# PCIe.net
KiCad netlist of a schematic drawn in Altium Designer
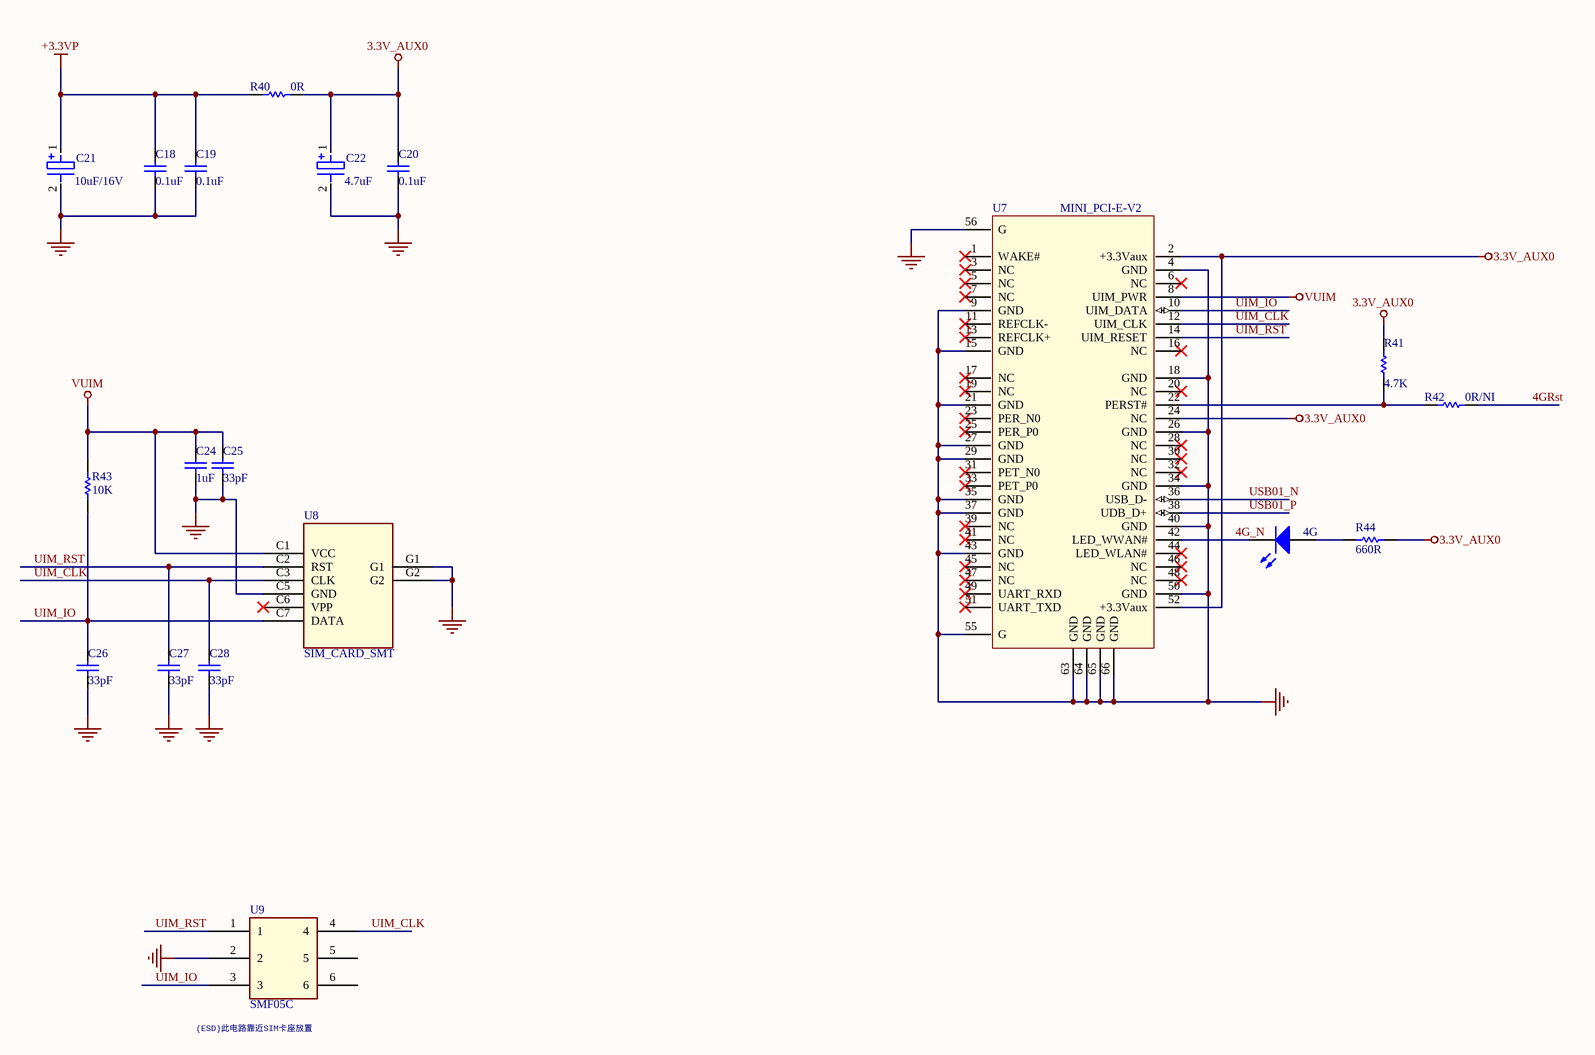
[diagram p0: PCIe.SchDoc]

(export (version "E")
  (design (tool "Eeschema 10.0.6"))
  (components
    (comp (ref "4G")
      (value "leds_0603")
      (footprint "0603LED")
      (libsource (lib "USB_SOUND") (part "leds_0603"))
    )
    (comp (ref "C18")
      (value "0.1uF")
      (footprint "C0603L")
      (description "Capacitor")
      (fields (field (name "Comment") "Cap Semi") (field (name "PUBLISHER") "Altium Limited"))
      (libsource (lib "Miscellaneous Devices") (part "Cap"))
    )
    (comp (ref "C19")
      (value "0.1uF")
      (footprint "C0603L")
      (description "Capacitor")
      (fields (field (name "Comment") "Cap Semi") (field (name "PUBLISHER") "Altium Limited"))
      (libsource (lib "Miscellaneous Devices") (part "Cap"))
    )
    (comp (ref "C20")
      (value "0.1uF")
      (footprint "C0603L")
      (description "Capacitor")
      (fields (field (name "Comment") "Cap Semi") (field (name "PUBLISHER") "Altium Limited"))
      (libsource (lib "Miscellaneous Devices") (part "Cap"))
    )
    (comp (ref "C21")
      (value "10uF/16V")
      (footprint "C0603L")
      (fields (field (name "Comment") "Cap Semi"))
      (libsource (lib "wooya_lib_footprint") (part "CAP3"))
    )
    (comp (ref "C22")
      (value "4.7uF")
      (footprint "C0603L")
      (fields (field (name "Comment") "Cap Semi"))
      (libsource (lib "wooya_lib_footprint") (part "CAP3"))
    )
    (comp (ref "C24")
      (value "1uF")
      (footprint "C0603L")
      (description "Capacitor (Semiconductor SIM Model)")
      (fields (field (name "Comment") "Cap Semi") (field (name "PUBLISHER") "Altium Limited"))
      (libsource (lib "Miscellaneous Devices") (part "Cap Semi"))
    )
    (comp (ref "C25")
      (value "33pF")
      (footprint "C0603L")
      (description "Capacitor (Semiconductor SIM Model)")
      (fields (field (name "Comment") "Cap Semi") (field (name "PUBLISHER") "Altium Limited"))
      (libsource (lib "Miscellaneous Devices") (part "Cap Semi"))
    )
    (comp (ref "C26")
      (value "33pF")
      (footprint "C0603L")
      (description "Capacitor (Semiconductor SIM Model)")
      (fields (field (name "Comment") "Cap Semi") (field (name "PUBLISHER") "Altium Limited"))
      (libsource (lib "Miscellaneous Devices") (part "Cap Semi"))
    )
    (comp (ref "C27")
      (value "33pF")
      (footprint "C0603L")
      (description "Capacitor (Semiconductor SIM Model)")
      (fields (field (name "Comment") "Cap Semi") (field (name "PUBLISHER") "Altium Limited"))
      (libsource (lib "Miscellaneous Devices") (part "Cap Semi"))
    )
    (comp (ref "C28")
      (value "33pF")
      (footprint "C0603L")
      (description "Capacitor (Semiconductor SIM Model)")
      (fields (field (name "Comment") "Cap Semi") (field (name "PUBLISHER") "Altium Limited"))
      (libsource (lib "Miscellaneous Devices") (part "Cap Semi"))
    )
    (comp (ref "R40")
      (value "0R")
      (footprint "R0603L")
      (description "Semiconductor Resistor")
      (fields (field (name "Comment") "Res Semi") (field (name "PUBLISHER") "Altium Limited"))
      (libsource (lib "Miscellaneous Devices") (part "Res Semi"))
    )
    (comp (ref "R41")
      (value "4.7K")
      (footprint "R0603L")
      (description "Semiconductor Resistor")
      (fields (field (name "Comment") "Res Semi") (field (name "PUBLISHER") "Altium Limited"))
      (libsource (lib "Miscellaneous Devices") (part "Res Semi"))
    )
    (comp (ref "R42")
      (value "0R/NI")
      (footprint "R0603L")
      (description "Semiconductor Resistor")
      (fields (field (name "Comment") "Res Semi") (field (name "PUBLISHER") "Altium Limited"))
      (libsource (lib "Miscellaneous Devices") (part "Res Semi"))
    )
    (comp (ref "R43")
      (value "10K")
      (footprint "R0603L")
      (description "Semiconductor Resistor")
      (fields (field (name "Comment") "Res Semi") (field (name "PUBLISHER") "Altium Limited"))
      (libsource (lib "Miscellaneous Devices") (part "Res Semi"))
    )
    (comp (ref "R44")
      (value "660R")
      (footprint "R0603L")
      (description "Semiconductor Resistor")
      (fields (field (name "Comment") "Res Semi") (field (name "PUBLISHER") "Altium Limited"))
      (libsource (lib "Miscellaneous Devices") (part "Res Semi"))
    )
    (comp (ref "U7")
      (value "MINI_PCI-E-V2")
      (footprint "MINI_PCI-E_V2")
      (libsource (lib "WOOYA_LIB_FOOTPRINT") (part "MINI_PCI-E-V2"))
    )
    (comp (ref "U8")
      (value "SIM_CARD_SMT")
      (footprint "SIM_CARD_SMT")
      (libsource (lib "wooya_lib_footprint") (part "SIM_CARD_SMT"))
    )
    (comp (ref "U9")
      (value "SMF05C")
      (footprint "SMF05C")
      (libsource (lib "wooya_lib_footprint") (part "SMF05C"))
    )
  )
  (nets
    (net (code "1") (name "+3.3VP") (class "Default")
      (node (ref "C18") (pin "2") (pinfunction "2_2") (pintype "passive"))
      (node (ref "C19") (pin "2") (pinfunction "2_2") (pintype "passive"))
      (node (ref "C21") (pin "1") (pinfunction "1_1") (pintype "passive"))
      (node (ref "R40") (pin "2") (pinfunction "2_2") (pintype "passive"))
    )
    (net (code "2") (name "/4GRst") (class "Default")
      (node (ref "R42") (pin "2") (pinfunction "2_2") (pintype "passive"))
    )
    (net (code "3") (name "/4G_N") (class "Default")
      (node (ref "4G") (pin "2") (pinfunction "K_2") (pintype "passive"))
      (node (ref "U7") (pin "42") (pinfunction "LED_WWAN#_42") (pintype "open_collector"))
    )
    (net (code "4") (name "/UIM_CLK") (class "Default")
      (node (ref "C28") (pin "1") (pinfunction "1_1") (pintype "passive"))
      (node (ref "U7") (pin "12") (pinfunction "UIM_CLK_12") (pintype "passive"))
      (node (ref "U8") (pin "C3") (pinfunction "CLK_C3") (pintype "passive"))
      (node (ref "U9") (pin "4") (pinfunction "4_4") (pintype "passive"))
    )
    (net (code "5") (name "/UIM_IO") (class "Default")
      (node (ref "C26") (pin "1") (pinfunction "1_1") (pintype "passive"))
      (node (ref "R43") (pin "1") (pinfunction "1_1") (pintype "passive"))
      (node (ref "U7") (pin "10") (pinfunction "UIM_DATA_10") (pintype "bidirectional"))
      (node (ref "U8") (pin "C7") (pinfunction "DATA_C7") (pintype "passive"))
      (node (ref "U9") (pin "3") (pinfunction "3_3") (pintype "passive"))
    )
    (net (code "6") (name "/UIM_RST") (class "Default")
      (node (ref "C27") (pin "1") (pinfunction "1_1") (pintype "passive"))
      (node (ref "U7") (pin "14") (pinfunction "UIM_RESET_14") (pintype "passive"))
      (node (ref "U8") (pin "C2") (pinfunction "RST_C2") (pintype "passive"))
      (node (ref "U9") (pin "1") (pinfunction "1_1") (pintype "passive"))
    )
    (net (code "7") (name "/USB01_N") (class "Default")
      (node (ref "U7") (pin "36") (pinfunction "USB_D-_36") (pintype "bidirectional"))
    )
    (net (code "8") (name "/USB01_P") (class "Default")
      (node (ref "U7") (pin "38") (pinfunction "UDB_D+_38") (pintype "bidirectional"))
    )
    (net (code "9") (name "3.3V_AUX0") (class "Default")
      (node (ref "C20") (pin "2") (pinfunction "2_2") (pintype "passive"))
      (node (ref "C22") (pin "1") (pinfunction "1_1") (pintype "passive"))
      (node (ref "R40") (pin "1") (pinfunction "1_1") (pintype "passive"))
      (node (ref "R41") (pin "1") (pinfunction "1_1") (pintype "passive"))
      (node (ref "R44") (pin "2") (pinfunction "2_2") (pintype "passive"))
      (node (ref "U7") (pin "2") (pinfunction "+3.3Vaux_2") (pintype "power_in"))
      (node (ref "U7") (pin "24") (pinfunction "NC_24") (pintype "power_in"))
      (node (ref "U7") (pin "52") (pinfunction "+3.3Vaux_52") (pintype "power_in"))
    )
    (net (code "10") (name "GND") (class "Default")
      (node (ref "C18") (pin "1") (pinfunction "1_1") (pintype "passive"))
      (node (ref "C19") (pin "1") (pinfunction "1_1") (pintype "passive"))
      (node (ref "C20") (pin "1") (pinfunction "1_1") (pintype "passive"))
      (node (ref "C21") (pin "2") (pinfunction "2_2") (pintype "passive"))
      (node (ref "C22") (pin "2") (pinfunction "2_2") (pintype "passive"))
      (node (ref "C24") (pin "2") (pinfunction "2_2") (pintype "passive"))
      (node (ref "C25") (pin "2") (pinfunction "2_2") (pintype "passive"))
      (node (ref "C26") (pin "2") (pinfunction "2_2") (pintype "passive"))
      (node (ref "C27") (pin "2") (pinfunction "2_2") (pintype "passive"))
      (node (ref "C28") (pin "2") (pinfunction "2_2") (pintype "passive"))
      (node (ref "U7") (pin "15") (pinfunction "GND_15") (pintype "passive"))
      (node (ref "U7") (pin "18") (pinfunction "GND_18") (pintype "passive"))
      (node (ref "U7") (pin "21") (pinfunction "GND_21") (pintype "passive"))
      (node (ref "U7") (pin "26") (pinfunction "GND_26") (pintype "passive"))
      (node (ref "U7") (pin "27") (pinfunction "GND_27") (pintype "passive"))
      (node (ref "U7") (pin "29") (pinfunction "GND_29") (pintype "passive"))
      (node (ref "U7") (pin "34") (pinfunction "GND_34") (pintype "passive"))
      (node (ref "U7") (pin "35") (pinfunction "GND_35") (pintype "passive"))
      (node (ref "U7") (pin "37") (pinfunction "GND_37") (pintype "passive"))
      (node (ref "U7") (pin "4") (pinfunction "GND_4") (pintype "passive"))
      (node (ref "U7") (pin "40") (pinfunction "GND_40") (pintype "passive"))
      (node (ref "U7") (pin "43") (pinfunction "GND_43") (pintype "passive"))
      (node (ref "U7") (pin "50") (pinfunction "GND_50") (pintype "passive"))
      (node (ref "U7") (pin "55") (pinfunction "G_55") (pintype "passive"))
      (node (ref "U7") (pin "56") (pinfunction "G_56") (pintype "passive"))
      (node (ref "U7") (pin "63") (pinfunction "GND_63") (pintype "passive"))
      (node (ref "U7") (pin "64") (pinfunction "GND_64") (pintype "passive"))
      (node (ref "U7") (pin "65") (pinfunction "GND_65") (pintype "passive"))
      (node (ref "U7") (pin "66") (pinfunction "GND_66") (pintype "passive"))
      (node (ref "U7") (pin "9") (pinfunction "GND_9") (pintype "passive"))
      (node (ref "U8") (pin "C5") (pinfunction "GND_C5") (pintype "passive"))
      (node (ref "U8") (pin "G1") (pinfunction "G1_G1") (pintype "passive"))
      (node (ref "U8") (pin "G2") (pinfunction "G2_G2") (pintype "passive"))
      (node (ref "U9") (pin "2") (pinfunction "2_2") (pintype "passive"))
    )
    (net (code "11") (name "Net-(4G-A)") (class "Default")
      (node (ref "4G") (pin "1") (pinfunction "A_1") (pintype "passive"))
      (node (ref "R44") (pin "1") (pinfunction "1_1") (pintype "passive"))
    )
    (net (code "12") (name "Net-(U7-PERST#)") (class "Default")
      (node (ref "R41") (pin "2") (pinfunction "2_2") (pintype "passive"))
      (node (ref "R42") (pin "1") (pinfunction "1_1") (pintype "passive"))
      (node (ref "U7") (pin "22") (pinfunction "PERST#_22") (pintype "passive"))
    )
    (net (code "13") (name "VUIM") (class "Default")
      (node (ref "C24") (pin "1") (pinfunction "1_1") (pintype "passive"))
      (node (ref "C25") (pin "1") (pinfunction "1_1") (pintype "passive"))
      (node (ref "R43") (pin "2") (pinfunction "2_2") (pintype "passive"))
      (node (ref "U7") (pin "8") (pinfunction "UIM_PWR_8") (pintype "passive"))
      (node (ref "U8") (pin "C1") (pinfunction "VCC_C1") (pintype "passive"))
    )
    (net (code "14") (name "unconnected-(U7-LED_WLAN#-Pad44)") (class "Default")
      (node (ref "U7") (pin "44") (pinfunction "LED_WLAN#_44") (pintype "open_collector+no_connect"))
    )
    (net (code "15") (name "unconnected-(U7-NC-Pad3)") (class "Default")
      (node (ref "U7") (pin "3") (pinfunction "NC_3") (pintype "open_collector+no_connect"))
    )
    (net (code "16") (name "unconnected-(U7-NC-Pad5)") (class "Default")
      (node (ref "U7") (pin "5") (pinfunction "NC_5") (pintype "open_collector+no_connect"))
    )
    (net (code "17") (name "unconnected-(U7-NC-Pad6)") (class "Default")
      (node (ref "U7") (pin "6") (pinfunction "NC_6") (pintype "open_collector+no_connect"))
    )
    (net (code "18") (name "unconnected-(U7-NC-Pad7)") (class "Default")
      (node (ref "U7") (pin "7") (pinfunction "NC_7") (pintype "open_collector+no_connect"))
    )
    (net (code "19") (name "unconnected-(U7-NC-Pad16)") (class "Default")
      (node (ref "U7") (pin "16") (pinfunction "NC_16") (pintype "open_collector+no_connect"))
    )
    (net (code "20") (name "unconnected-(U7-NC-Pad17)") (class "Default")
      (node (ref "U7") (pin "17") (pinfunction "NC_17") (pintype "open_collector+no_connect"))
    )
    (net (code "21") (name "unconnected-(U7-NC-Pad19)") (class "Default")
      (node (ref "U7") (pin "19") (pinfunction "NC_19") (pintype "open_collector+no_connect"))
    )
    (net (code "22") (name "unconnected-(U7-NC-Pad20)") (class "Default")
      (node (ref "U7") (pin "20") (pinfunction "NC_20") (pintype "open_collector+no_connect"))
    )
    (net (code "23") (name "unconnected-(U7-NC-Pad28)") (class "Default")
      (node (ref "U7") (pin "28") (pinfunction "NC_28") (pintype "open_collector+no_connect"))
    )
    (net (code "24") (name "unconnected-(U7-NC-Pad30)") (class "Default")
      (node (ref "U7") (pin "30") (pinfunction "NC_30") (pintype "open_collector+no_connect"))
    )
    (net (code "25") (name "unconnected-(U7-NC-Pad32)") (class "Default")
      (node (ref "U7") (pin "32") (pinfunction "NC_32") (pintype "open_collector+no_connect"))
    )
    (net (code "26") (name "unconnected-(U7-NC-Pad39)") (class "Default")
      (node (ref "U7") (pin "39") (pinfunction "NC_39") (pintype "power_in+no_connect"))
    )
    (net (code "27") (name "unconnected-(U7-NC-Pad41)") (class "Default")
      (node (ref "U7") (pin "41") (pinfunction "NC_41") (pintype "power_in+no_connect"))
    )
    (net (code "28") (name "unconnected-(U7-NC-Pad45)") (class "Default")
      (node (ref "U7") (pin "45") (pinfunction "NC_45") (pintype "open_collector+no_connect"))
    )
    (net (code "29") (name "unconnected-(U7-NC-Pad46)") (class "Default")
      (node (ref "U7") (pin "46") (pinfunction "NC_46") (pintype "open_collector+no_connect"))
    )
    (net (code "30") (name "unconnected-(U7-NC-Pad47)") (class "Default")
      (node (ref "U7") (pin "47") (pinfunction "NC_47") (pintype "open_collector+no_connect"))
    )
    (net (code "31") (name "unconnected-(U7-NC-Pad48)") (class "Default")
      (node (ref "U7") (pin "48") (pinfunction "NC_48") (pintype "open_collector+no_connect"))
    )
    (net (code "32") (name "unconnected-(U7-PER_N0-Pad23)") (class "Default")
      (node (ref "U7") (pin "23") (pinfunction "PER_N0_23") (pintype "open_collector+no_connect"))
    )
    (net (code "33") (name "unconnected-(U7-PER_P0-Pad25)") (class "Default")
      (node (ref "U7") (pin "25") (pinfunction "PER_P0_25") (pintype "open_collector+no_connect"))
    )
    (net (code "34") (name "unconnected-(U7-PET_N0-Pad31)") (class "Default")
      (node (ref "U7") (pin "31") (pinfunction "PET_N0_31") (pintype "open_collector+no_connect"))
    )
    (net (code "35") (name "unconnected-(U7-PET_P0-Pad33)") (class "Default")
      (node (ref "U7") (pin "33") (pinfunction "PET_P0_33") (pintype "open_collector+no_connect"))
    )
    (net (code "36") (name "unconnected-(U7-REFCLK+-Pad13)") (class "Default")
      (node (ref "U7") (pin "13") (pinfunction "REFCLK+_13") (pintype "open_collector+no_connect"))
    )
    (net (code "37") (name "unconnected-(U7-REFCLK--Pad11)") (class "Default")
      (node (ref "U7") (pin "11") (pinfunction "REFCLK-_11") (pintype "open_collector+no_connect"))
    )
    (net (code "38") (name "unconnected-(U7-UART_RXD-Pad49)") (class "Default")
      (node (ref "U7") (pin "49") (pinfunction "UART_RXD_49") (pintype "open_collector+no_connect"))
    )
    (net (code "39") (name "unconnected-(U7-UART_TXD-Pad51)") (class "Default")
      (node (ref "U7") (pin "51") (pinfunction "UART_TXD_51") (pintype "open_collector+no_connect"))
    )
    (net (code "40") (name "unconnected-(U7-WAKE#-Pad1)") (class "Default")
      (node (ref "U7") (pin "1") (pinfunction "WAKE#_1") (pintype "open_collector+no_connect"))
    )
    (net (code "41") (name "unconnected-(U8-VPP-PadC6)") (class "Default")
      (node (ref "U8") (pin "C6") (pinfunction "VPP_C6") (pintype "passive+no_connect"))
    )
    (net (code "42") (name "unconnected-(U9-Pad5)") (class "Default")
      (node (ref "U9") (pin "5") (pinfunction "5_5") (pintype "passive"))
    )
    (net (code "43") (name "unconnected-(U9-Pad6)") (class "Default")
      (node (ref "U9") (pin "6") (pinfunction "6_6") (pintype "passive"))
    )
  )
)
